# tft_display.net
KiCad netlist of a schematic drawn in Altium Designer
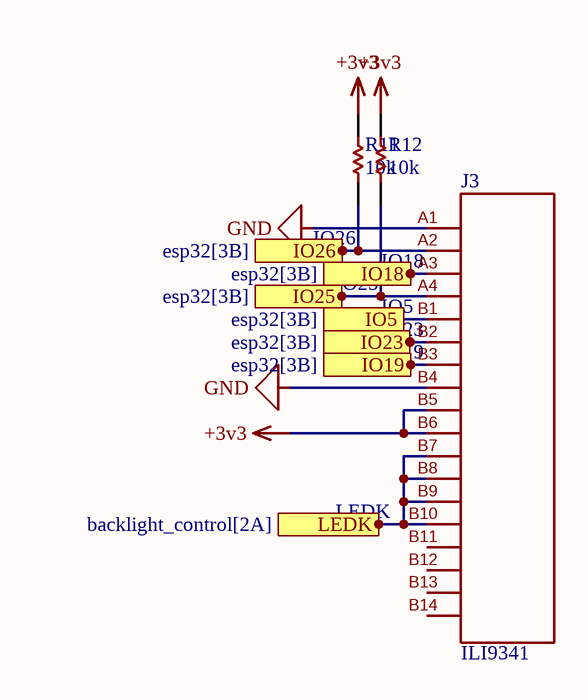
[diagram p0: tft_display.SchDoc]

(export (version "E")
  (design (tool "Eeschema 10.0.6"))
  (components
    (comp (ref "J3")
      (value "ILI9341")
      (footprint "ILI9341")
      (libsource (lib "Thermal_Camera") (part "ILI9341"))
    )
    (comp (ref "R11")
      (value "10k")
      (footprint "RESC2013X70X40NL20T20")
      (description "Chip Resistor, 1 KOhm, +/- 1%, 125 mW, -55 to 155 degC, 0805 (2012 Metric), RoHS, Tape and Reel")
      (fields (field (name "TOLERANCE") "1%") (field (name "MANUFACTURER") "Yageo"))
      (libsource (lib "Thermal_Camera") (part "CMP-2100-03671-1"))
    )
    (comp (ref "R12")
      (value "10k")
      (footprint "RESC2013X70X40NL20T20")
      (description "Chip Resistor, 1 KOhm, +/- 1%, 125 mW, -55 to 155 degC, 0805 (2012 Metric), RoHS, Tape and Reel")
      (fields (field (name "TOLERANCE") "1%") (field (name "MANUFACTURER") "Yageo"))
      (libsource (lib "Thermal_Camera") (part "CMP-2100-03671-1"))
    )
  )
  (nets
    (net (code "1") (name "+3v3") (class "Default")
      (node (ref "J3") (pin "B5") (pinfunction "VDD_B5") (pintype "passive"))
      (node (ref "J3") (pin "B6") (pinfunction "LEDA_B6") (pintype "passive"))
      (node (ref "R11") (pin "2") (pinfunction "2_2") (pintype "passive"))
      (node (ref "R12") (pin "2") (pinfunction "2_2") (pintype "passive"))
    )
    (net (code "2") (name "/IO5") (class "Default")
      (node (ref "J3") (pin "B1") (pinfunction "CS_B1") (pintype "passive"))
    )
    (net (code "3") (name "/IO18") (class "Default")
      (node (ref "J3") (pin "A3") (pinfunction "SCL_A3") (pintype "passive"))
    )
    (net (code "4") (name "/IO19") (class "Default")
      (node (ref "J3") (pin "B3") (pinfunction "SDO_B3") (pintype "passive"))
    )
    (net (code "5") (name "/IO23") (class "Default")
      (node (ref "J3") (pin "B2") (pinfunction "SDA_B2") (pintype "passive"))
    )
    (net (code "6") (name "/IO25") (class "Default")
      (node (ref "J3") (pin "A4") (pinfunction "RS_A4") (pintype "passive"))
      (node (ref "R12") (pin "1") (pinfunction "1_1") (pintype "passive"))
    )
    (net (code "7") (name "/IO26") (class "Default")
      (node (ref "J3") (pin "A2") (pinfunction "RESET_A2") (pintype "passive"))
      (node (ref "R11") (pin "1") (pinfunction "1_1") (pintype "passive"))
    )
    (net (code "8") (name "/LEDK") (class "Default")
      (node (ref "J3") (pin "B10") (pinfunction "LEDK4_B10") (pintype "passive"))
      (node (ref "J3") (pin "B7") (pinfunction "LEDK1_B7") (pintype "passive"))
      (node (ref "J3") (pin "B8") (pinfunction "LEDK2_B8") (pintype "passive"))
      (node (ref "J3") (pin "B9") (pinfunction "LEDK3_B9") (pintype "passive"))
    )
    (net (code "9") (name "GND") (class "Default")
      (node (ref "J3") (pin "A1") (pinfunction "GND_A1") (pintype "passive"))
      (node (ref "J3") (pin "B4") (pinfunction "GND_B4") (pintype "passive"))
    )
    (net (code "10") (name "unconnected-(J3-XL-PadB11)") (class "Default")
      (node (ref "J3") (pin "B11") (pinfunction "XL_B11") (pintype "passive"))
    )
    (net (code "11") (name "unconnected-(J3-XR-PadB13)") (class "Default")
      (node (ref "J3") (pin "B13") (pinfunction "XR_B13") (pintype "passive"))
    )
    (net (code "12") (name "unconnected-(J3-YD-PadB14)") (class "Default")
      (node (ref "J3") (pin "B14") (pinfunction "YD_B14") (pintype "passive"))
    )
    (net (code "13") (name "unconnected-(J3-YU-PadB12)") (class "Default")
      (node (ref "J3") (pin "B12") (pinfunction "YU_B12") (pintype "passive"))
    )
  )
)
